# High_Pass_Filter.net
KiCad netlist of a schematic drawn in Altium Designer
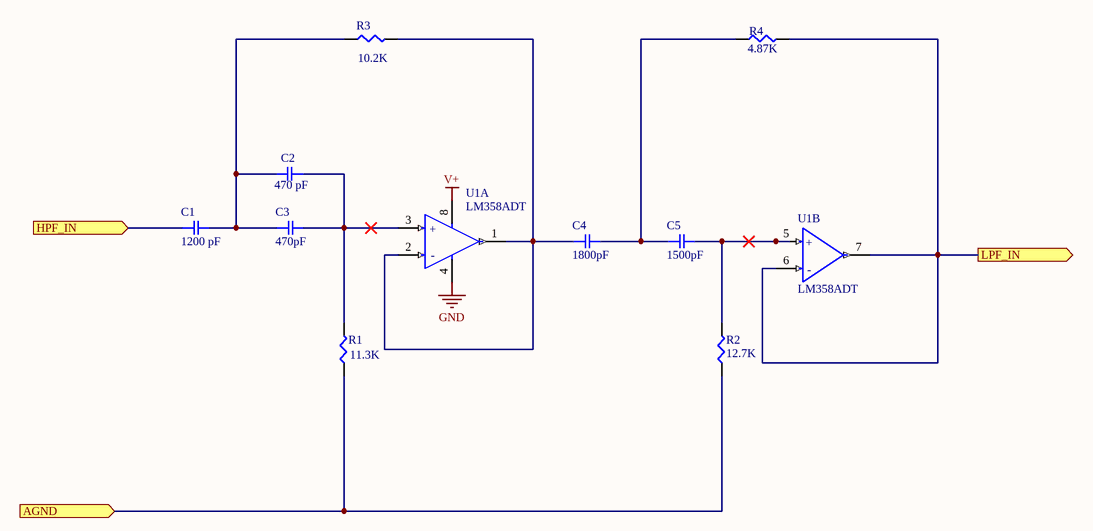
[diagram p0: High Pass Filter.SchDoc]

(export (version "E")
  (design (tool "Eeschema 10.0.6"))
  (components
    (comp (ref "C1")
      (value "1200 pF")
      (footprint "SMD-0805C")
      (fields
        (field (name "MANUFACTURER") "KEMET")
        (field (name "MANUFACTURER PART NUMBER") "C0805C122J2GAC7800")
      )
      (libsource (lib "capacitor_murata_0805") (part "GRM216R71E122KA01D"))
    )
    (comp (ref "C2")
      (value "470 pF")
      (footprint "SMD-0805C")
      (fields
        (field (name "MANUFACTURER") "KEMET")
        (field (name "MANUFACTURER PART NUMBER") "C0805C471J1GAC7800")
      )
      (libsource (lib "capacitor_murata_0805") (part "GCM2165C1H471JA16D"))
    )
    (comp (ref "C3")
      (value "470pF")
      (footprint "SMD-0805C")
      (fields
        (field (name "MANUFACTURER") "KEMET")
        (field (name "MANUFACTURER PART NUMBER") "C0805C471J1GAC7800")
      )
      (libsource (lib "capacitor_murata_0805") (part "GCM2165C1H471JA16D"))
    )
    (comp (ref "C4")
      (value "1800pF")
      (footprint "SMD-0805C")
      (fields
        (field (name "MANUFACTURER") "KEMET")
        (field (name "MANUFACTURER PART NUMBER") "C0805C182K5RAC7800")
      )
      (libsource (lib "capacitor_murata_0805") (part "GRM216R71E182KA01D"))
    )
    (comp (ref "C5")
      (value "1500pF")
      (footprint "SMD-0805C")
      (fields
        (field (name "MANUFACTURER") "KEMET")
        (field (name "MANUFACTURER PART NUMBER") "C0805C152JAGAC7800")
      )
      (libsource (lib "capacitor_murata_0805") (part "GCJ216R71H152KA01D"))
    )
    (comp (ref "R1")
      (value "11.3K")
      (footprint "SMD-0805-RES")
      (fields
        (field (name "MANUFACTURER") "Stackpole Electronics Inc")
        (field (name "MANUFACTURER PART NUMBER") "RNCF0805DTE11K3")
      )
      (libsource (lib "Panasonic_resistor_0805") (part "ERJ-6ENF1132V"))
    )
    (comp (ref "R2")
      (value "12.7K")
      (footprint "SMD-0805-RES")
      (fields
        (field (name "MANUFACTURER") "Stackpole Electronics Inc")
        (field (name "MANUFACTURER PART NUMBER") "RNCF0805DTE12K7")
      )
      (libsource (lib "Panasonic_resistor_0805") (part "ERJ-6ENF1272V"))
    )
    (comp (ref "R3")
      (value "10.2K")
      (footprint "SMD-0805-RES")
      (fields
        (field (name "MANUFACTURER") "Stackpole Electronics Inc")
        (field (name "MANUFACTURER PART NUMBER") "RNCF0805DTE10K2")
      )
      (libsource (lib "Panasonic_resistor_0805") (part "ERJ-6ENF1022V"))
    )
    (comp (ref "R4")
      (value "4.87K")
      (footprint "SMD-0805-RES")
      (fields
        (field (name "MANUFACTURER") "Stackpole Electronics Inc")
        (field (name "MANUFACTURER PART NUMBER") "RMCF0805FT4K87")
      )
      (libsource (lib "Panasonic_resistor_0805") (part "ERJ-6ENF4871V"))
    )
    (comp (ref "U1")
      (value "LM358ADT")
      (footprint "FP-SO8-IPC_C")
      (fields
        (field (name "MANUFACTURER PART NUMBER") "LM358WDT")
        (field (name "MANUFACTURER") "STMicroelectronics")
      )
      (libsource (lib "Altium Content Vault") (part "9f386d5a0a155305257da89b0c2f71e"))
    )
  )
  (nets
    (net (code "1") (name "/AGND") (class "Default")
      (node (ref "R1") (pin "1") (pinfunction "1_1") (pintype "passive"))
      (node (ref "R2") (pin "1") (pinfunction "1_1") (pintype "passive"))
    )
    (net (code "2") (name "/HPF_IN") (class "Default")
      (node (ref "C1") (pin "1") (pinfunction "1_1") (pintype "passive"))
    )
    (net (code "3") (name "/LPF_IN") (class "Default")
      (node (ref "R4") (pin "2") (pinfunction "2_2") (pintype "passive"))
      (node (ref "U1") (pin "6") (pinfunction "In2-_6") (pintype "input"))
      (node (ref "U1") (pin "7") (pinfunction "Out2_7") (pintype "output"))
    )
    (net (code "4") (name "GND") (class "Default")
      (node (ref "U1") (pin "4") (pinfunction "VCC-_4") (pintype "power_in"))
    )
    (net (code "5") (name "Net-(C1-Pad2)") (class "Default")
      (node (ref "C1") (pin "2") (pinfunction "2_2") (pintype "passive"))
      (node (ref "C2") (pin "2") (pinfunction "2_2") (pintype "passive"))
      (node (ref "C3") (pin "1") (pinfunction "1_1") (pintype "passive"))
      (node (ref "R3") (pin "1") (pinfunction "1_1") (pintype "passive"))
    )
    (net (code "6") (name "Net-(C4-Pad2)") (class "Default")
      (node (ref "C4") (pin "2") (pinfunction "2_2") (pintype "passive"))
      (node (ref "C5") (pin "1") (pinfunction "1_1") (pintype "passive"))
      (node (ref "R4") (pin "1") (pinfunction "1_1") (pintype "passive"))
    )
    (net (code "7") (name "Net-(U1A-In1+)") (class "Default")
      (node (ref "C2") (pin "1") (pinfunction "1_1") (pintype "passive"))
      (node (ref "C3") (pin "2") (pinfunction "2_2") (pintype "passive"))
      (node (ref "R1") (pin "2") (pinfunction "2_2") (pintype "passive"))
      (node (ref "U1") (pin "3") (pinfunction "In1+_3") (pintype "input"))
    )
    (net (code "8") (name "Net-(U1A-In1-)") (class "Default")
      (node (ref "C4") (pin "1") (pinfunction "1_1") (pintype "passive"))
      (node (ref "R3") (pin "2") (pinfunction "2_2") (pintype "passive"))
      (node (ref "U1") (pin "1") (pinfunction "Out1_1") (pintype "output"))
      (node (ref "U1") (pin "2") (pinfunction "In1-_2") (pintype "input"))
    )
    (net (code "9") (name "Net-(U1B-In2+)") (class "Default")
      (node (ref "C5") (pin "2") (pinfunction "2_2") (pintype "passive"))
      (node (ref "R2") (pin "2") (pinfunction "2_2") (pintype "passive"))
      (node (ref "U1") (pin "5") (pinfunction "In2+_5") (pintype "input"))
    )
    (net (code "10") (name "V+") (class "Default")
      (node (ref "U1") (pin "8") (pinfunction "VCC+_8") (pintype "power_in"))
    )
  )
)
